# template.net
KiCad netlist of a schematic drawn in EAGLE
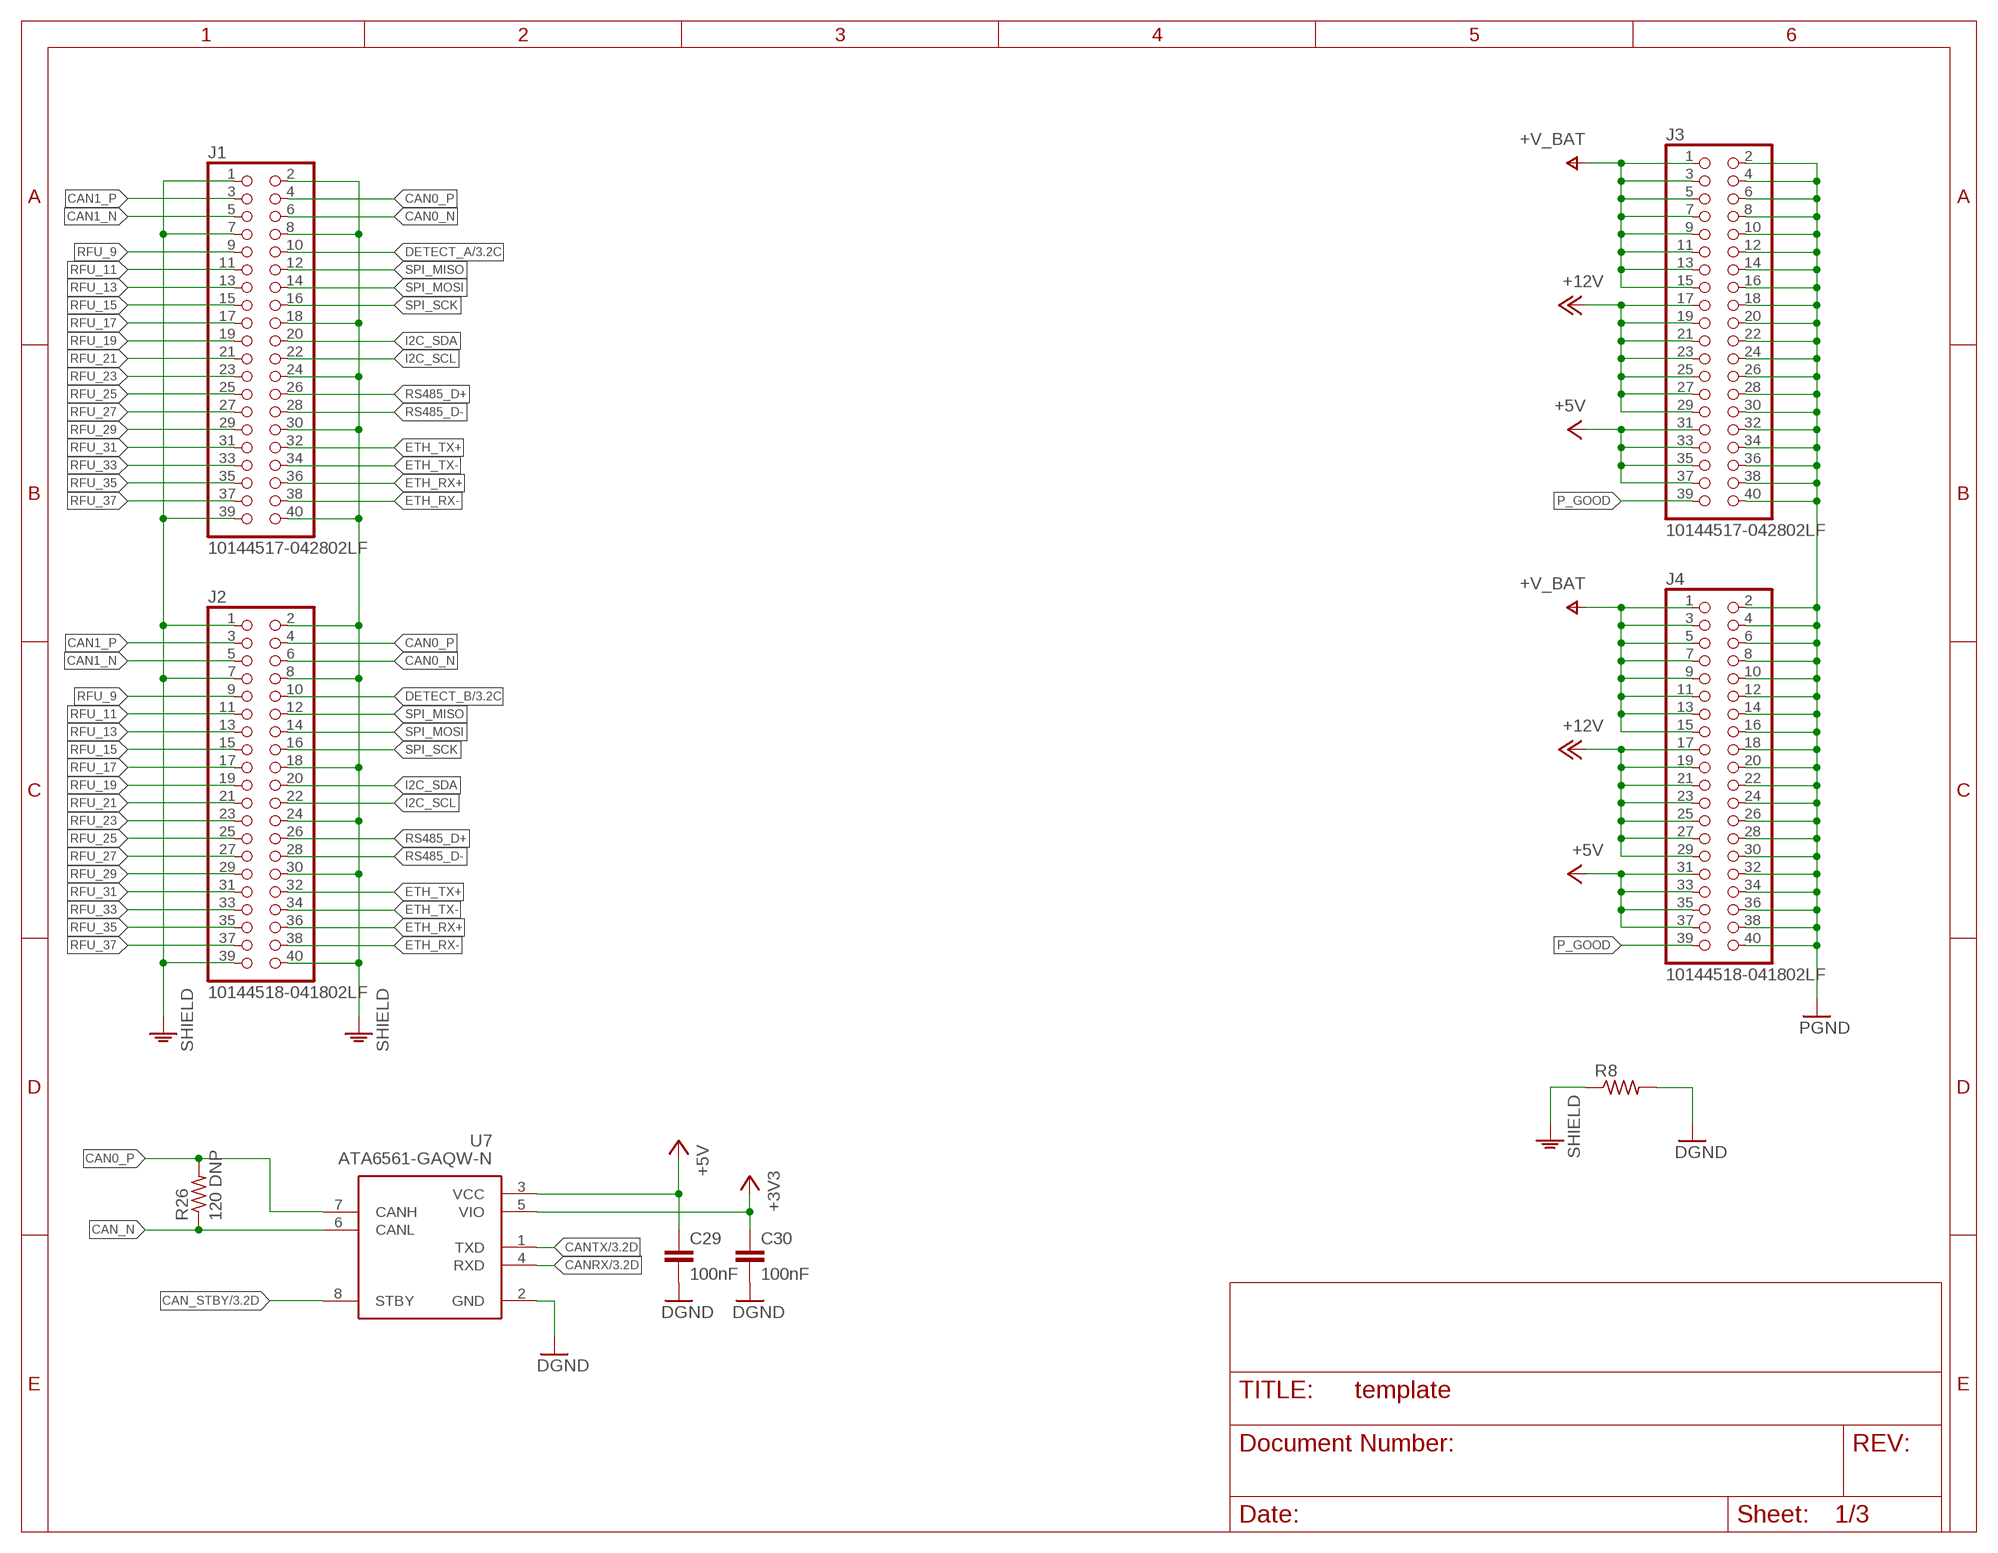
[diagram p0: schematic, sheet 1]
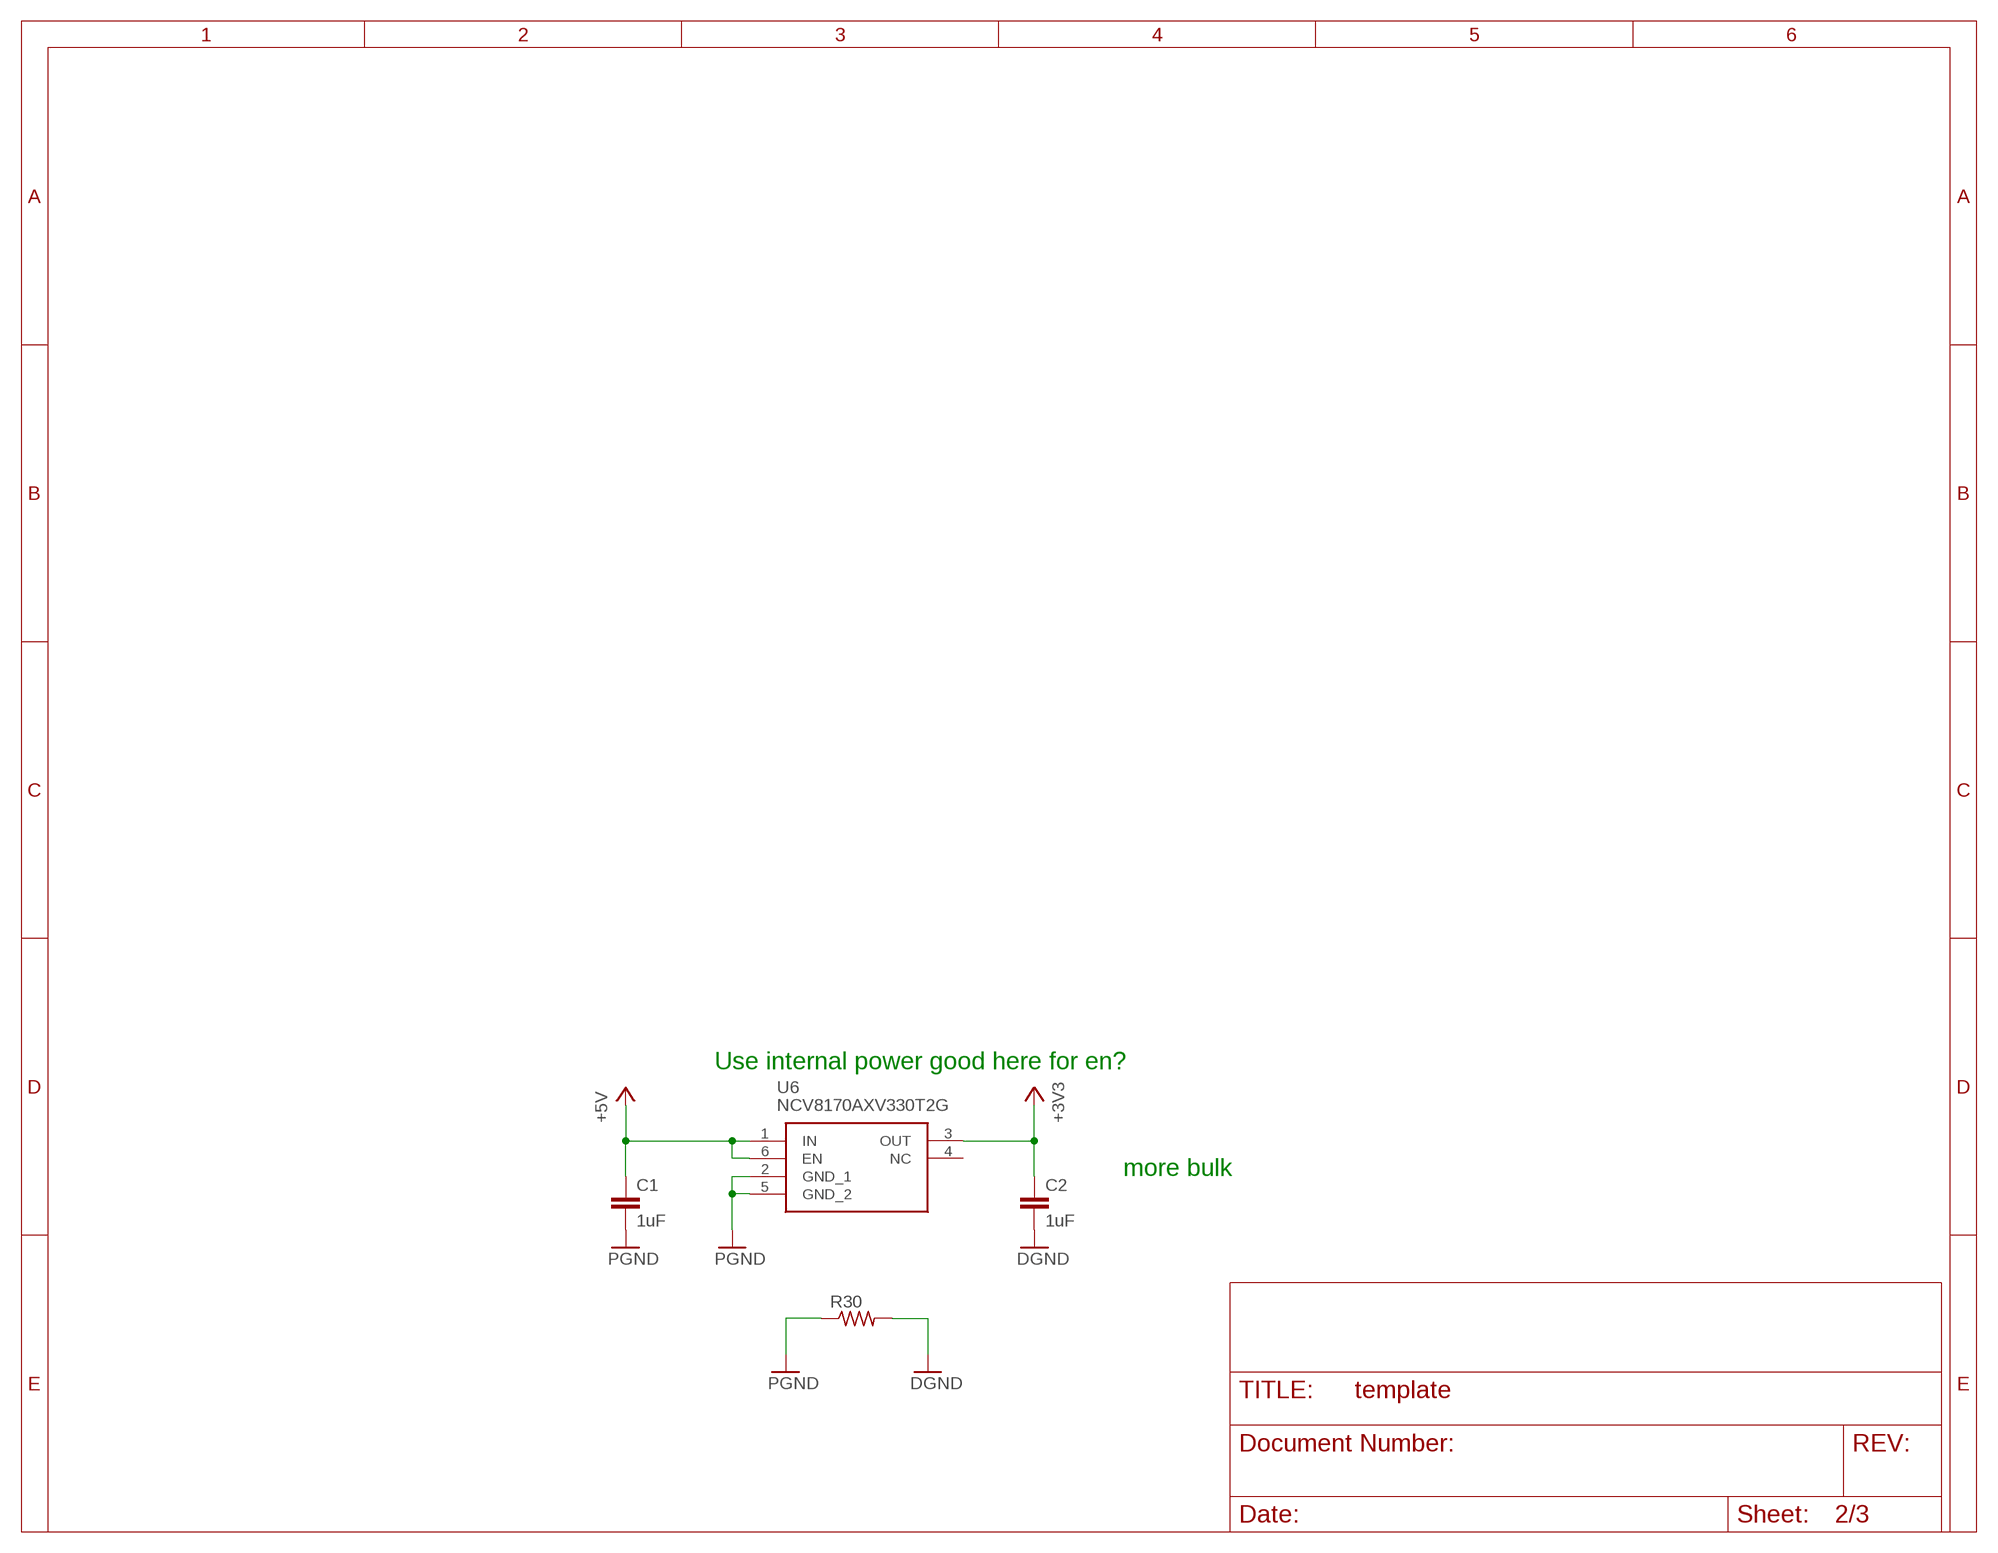
[diagram p1: schematic, sheet 2]
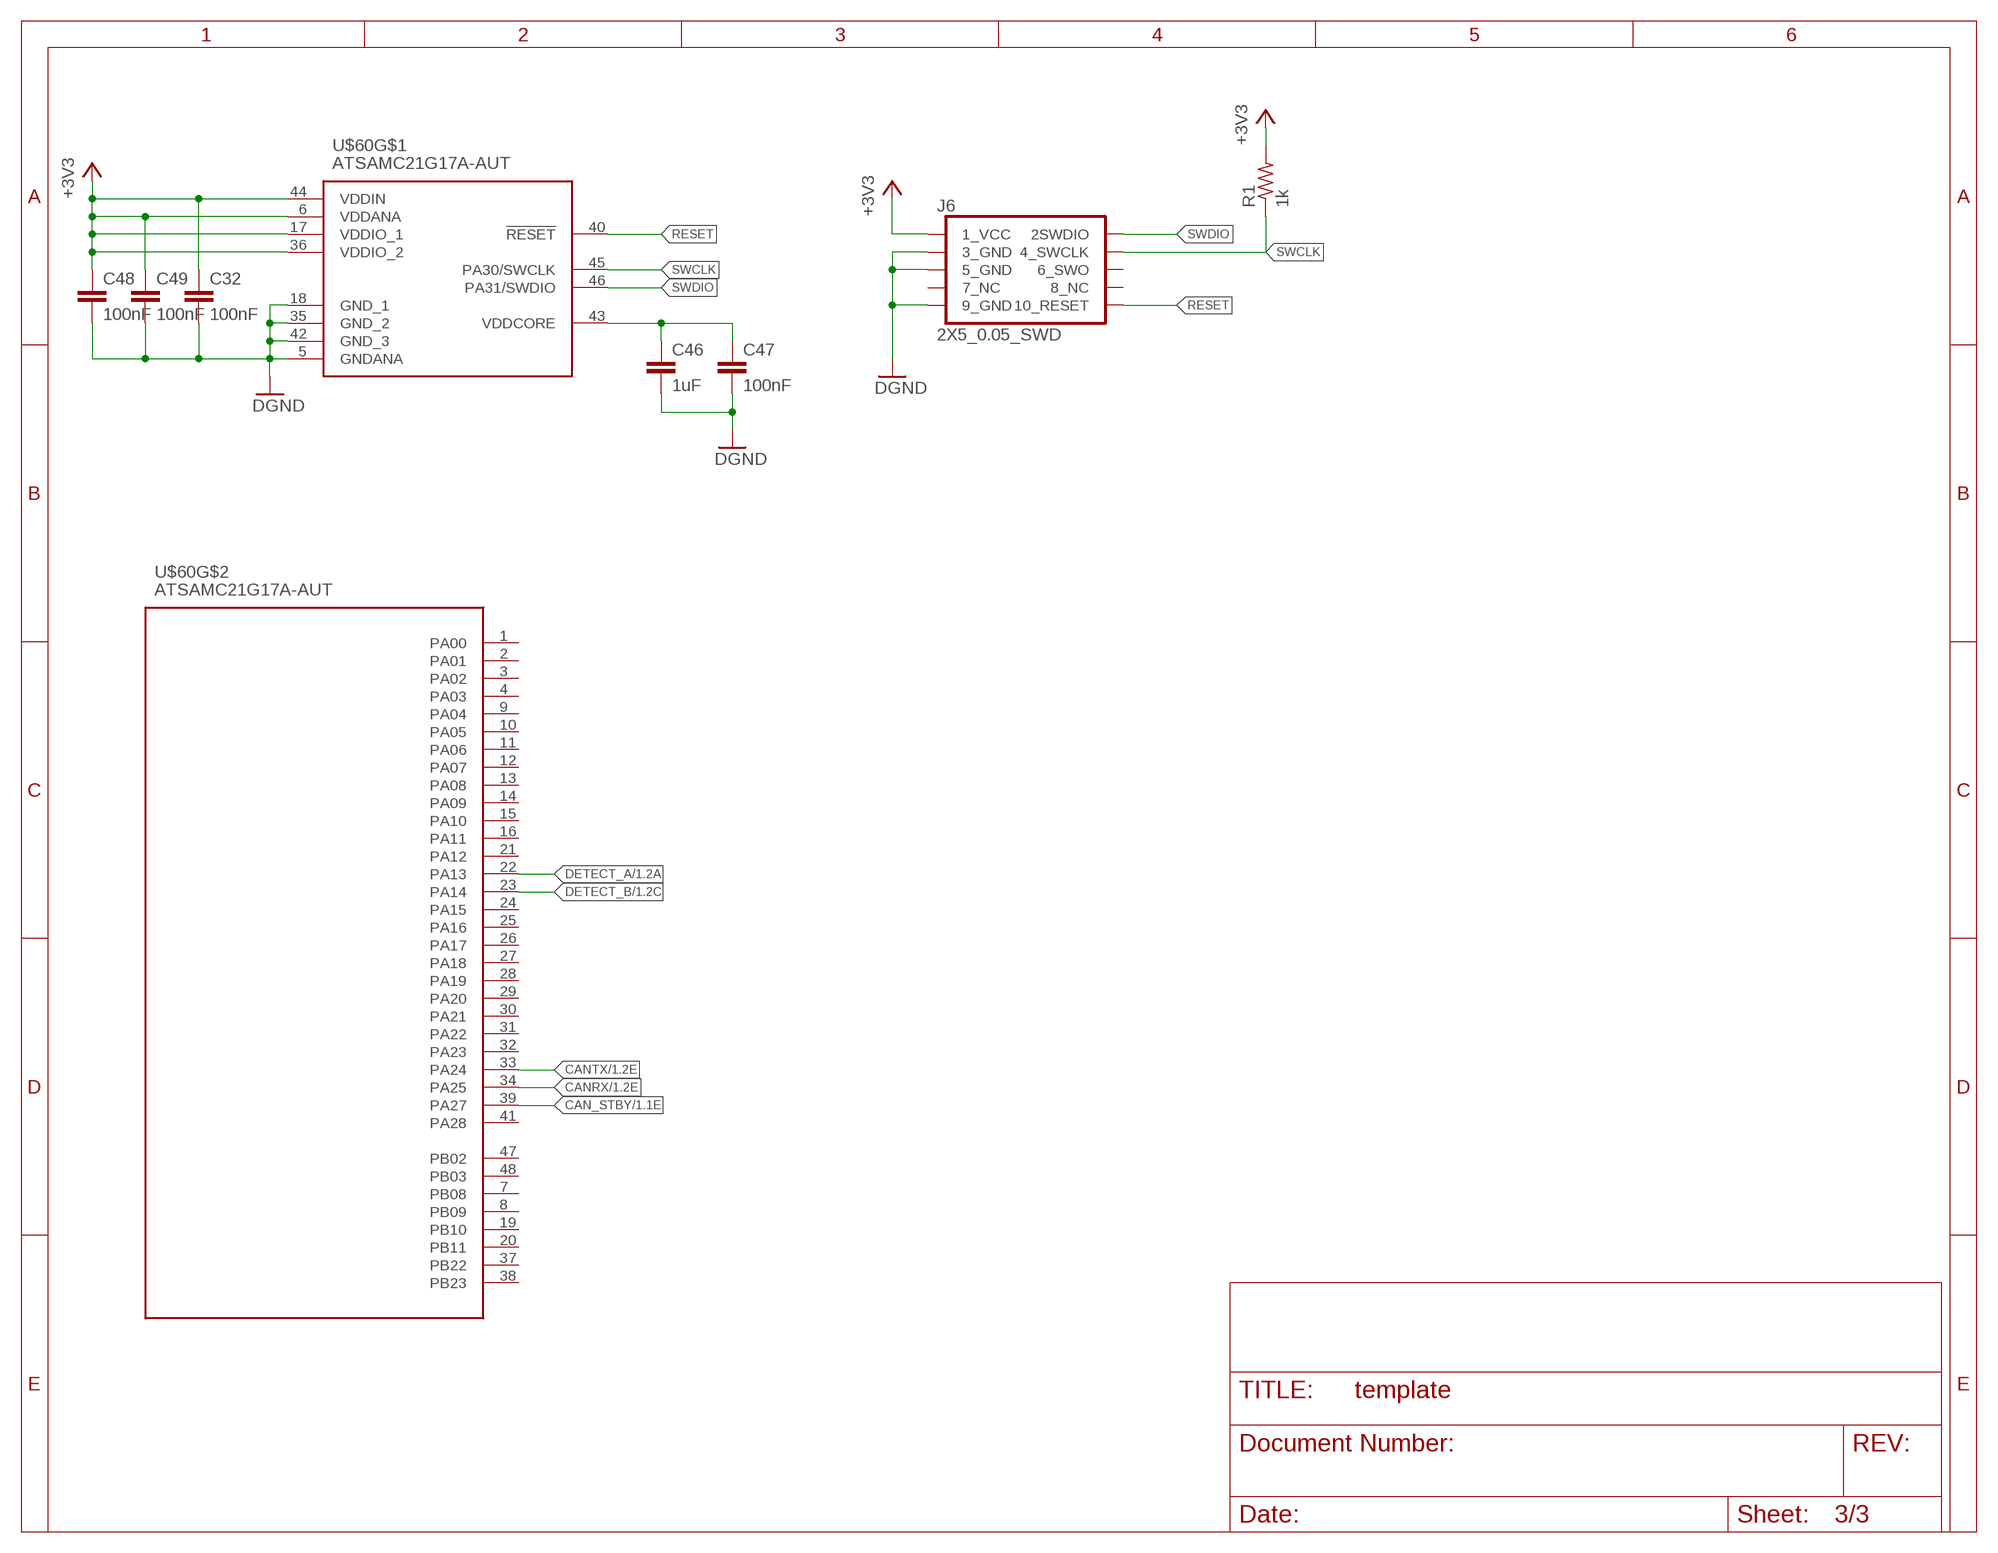
[diagram p2: schematic, sheet 3]

(export (version "E")
  (design (tool "Eeschema 10.0.6"))
  (components
    (comp (ref "C32")
      (value "100nF")
      (footprint "eagle-import:C0805")
      (libsource (lib "eagle-import") (part "C-EUC0805"))
    )
    (comp (ref "C46")
      (value "1uF")
      (footprint "eagle-import:C0805")
      (libsource (lib "eagle-import") (part "C-EUC0805"))
    )
    (comp (ref "C47")
      (value "100nF")
      (footprint "eagle-import:C0805")
      (libsource (lib "eagle-import") (part "C-EUC0805"))
    )
    (comp (ref "C48")
      (value "100nF")
      (footprint "eagle-import:C0805")
      (libsource (lib "eagle-import") (part "C-EUC0805"))
    )
    (comp (ref "C49")
      (value "100nF")
      (footprint "eagle-import:C0805")
      (libsource (lib "eagle-import") (part "C-EUC0805"))
    )
    (comp (ref "J6")
      (value "2X5_0.05_SWD")
      (footprint "eagle-import:2X5_RIGHT")
      (libsource (lib "eagle-import") (part "2X5_0.05_SWD"))
    )
    (comp (ref "R1")
      (value "1k")
      (footprint "eagle-import:R0402")
      (libsource (lib "eagle-import") (part "R-US_R0402"))
    )
    (comp (ref "U$60")
      (value "ATSAMC21G17A-AUT")
      (footprint "eagle-import:QFP50P900X900X120-48N")
      (libsource (lib "eagle-import") (part "ATSAMC21G17A-AUT"))
    )
    (comp (ref "C1")
      (value "1uF")
      (footprint "eagle-import:C0603")
      (libsource (lib "eagle-import") (part "C-EUC0603"))
    )
    (comp (ref "C2")
      (value "1uF")
      (footprint "eagle-import:C0603")
      (libsource (lib "eagle-import") (part "C-EUC0603"))
    )
    (comp (ref "R30")
      (value "R-US_R0402")
      (footprint "eagle-import:R0402")
      (libsource (lib "eagle-import") (part "R-US_R0402"))
    )
    (comp (ref "U6")
      (value "NCV8170AXV330T2G")
      (footprint "eagle-import:SOTFL50P160X60-6N")
      (fields (field (name "MOUSER_PART_NUMBER") "863-NCV8170AXV330T2G"))
      (libsource (lib "eagle-import") (part "NCV8170AXV330T2G"))
    )
    (comp (ref "C29")
      (value "100nF")
      (footprint "eagle-import:C0402")
      (libsource (lib "eagle-import") (part "C-EUC0402"))
    )
    (comp (ref "C30")
      (value "100nF")
      (footprint "eagle-import:C0402")
      (libsource (lib "eagle-import") (part "C-EUC0402"))
    )
    (comp (ref "J1")
      (value "10144517-042802LF")
      (footprint "eagle-import:10144517-042802LF")
      (libsource (lib "eagle-import") (part "10144517-042802LF"))
    )
    (comp (ref "J2")
      (value "10144518-041802LF")
      (footprint "eagle-import:10144518-041802LF")
      (libsource (lib "eagle-import") (part "10144518-041802LF"))
    )
    (comp (ref "J3")
      (value "10144517-042802LF")
      (footprint "eagle-import:10144517-042802LF")
      (libsource (lib "eagle-import") (part "10144517-042802LF"))
    )
    (comp (ref "J4")
      (value "10144518-041802LF")
      (footprint "eagle-import:10144518-041802LF")
      (libsource (lib "eagle-import") (part "10144518-041802LF"))
    )
    (comp (ref "R8")
      (value "R-US_R0402")
      (footprint "eagle-import:R0402")
      (libsource (lib "eagle-import") (part "R-US_R0402"))
    )
    (comp (ref "R26")
      (value "120 DNP")
      (footprint "eagle-import:R0402")
      (libsource (lib "eagle-import") (part "R-US_R0402"))
    )
    (comp (ref "U7")
      (value "ATA6561-GAQW-N")
      (footprint "eagle-import:SOIC127P600X175-8N")
      (fields (field (name "MOUSER_PART_NUMBER") "579-ATA6561-GAQW-N"))
      (libsource (lib "eagle-import") (part "ATA6561-GAQW-N"))
    )
  )
  (nets
    (net (code "1") (name "+3V3") (class "Default")
      (node (ref "C2") (pin "1") (pinfunction "1_1") (pintype "passive"))
      (node (ref "C30") (pin "1") (pinfunction "1_1") (pintype "passive"))
      (node (ref "C32") (pin "1") (pinfunction "1_1") (pintype "passive"))
      (node (ref "C48") (pin "1") (pinfunction "1_1") (pintype "passive"))
      (node (ref "C49") (pin "1") (pinfunction "1_1") (pintype "passive"))
      (node (ref "J6") (pin "1") (pinfunction "1_VCC_1") (pintype "passive"))
      (node (ref "R1") (pin "2") (pinfunction "2_2") (pintype "passive"))
      (node (ref "U$60") (pin "17") (pinfunction "VDDIO_1_17") (pintype "bidirectional"))
      (node (ref "U$60") (pin "36") (pinfunction "VDDIO_2_36") (pintype "bidirectional"))
      (node (ref "U$60") (pin "44") (pinfunction "VDDIN_44") (pintype "power_in"))
      (node (ref "U$60") (pin "6") (pinfunction "VDDANA_6") (pintype "power_in"))
      (node (ref "U6") (pin "3") (pinfunction "OUT_3") (pintype "bidirectional"))
      (node (ref "U7") (pin "5") (pinfunction "VIO_5") (pintype "bidirectional"))
    )
    (net (code "2") (name "+5V") (class "Default")
      (node (ref "C1") (pin "1") (pinfunction "1_1") (pintype "passive"))
      (node (ref "C29") (pin "1") (pinfunction "1_1") (pintype "passive"))
      (node (ref "J3") (pin "31") (pinfunction "31_31") (pintype "passive"))
      (node (ref "J3") (pin "33") (pinfunction "33_33") (pintype "passive"))
      (node (ref "J3") (pin "35") (pinfunction "35_35") (pintype "passive"))
      (node (ref "J3") (pin "37") (pinfunction "37_37") (pintype "passive"))
      (node (ref "J4") (pin "31") (pinfunction "31_31") (pintype "passive"))
      (node (ref "J4") (pin "33") (pinfunction "33_33") (pintype "passive"))
      (node (ref "J4") (pin "35") (pinfunction "35_35") (pintype "passive"))
      (node (ref "J4") (pin "37") (pinfunction "37_37") (pintype "passive"))
      (node (ref "U6") (pin "1") (pinfunction "IN_1") (pintype "bidirectional"))
      (node (ref "U6") (pin "6") (pinfunction "EN_6") (pintype "bidirectional"))
      (node (ref "U7") (pin "3") (pinfunction "VCC_3") (pintype "bidirectional"))
    )
    (net (code "3") (name "+12V") (class "Default")
      (node (ref "J3") (pin "17") (pinfunction "17_17") (pintype "passive"))
      (node (ref "J3") (pin "19") (pinfunction "19_19") (pintype "passive"))
      (node (ref "J3") (pin "21") (pinfunction "21_21") (pintype "passive"))
      (node (ref "J3") (pin "23") (pinfunction "23_23") (pintype "passive"))
      (node (ref "J3") (pin "25") (pinfunction "25_25") (pintype "passive"))
      (node (ref "J3") (pin "27") (pinfunction "27_27") (pintype "passive"))
      (node (ref "J3") (pin "29") (pinfunction "29_29") (pintype "passive"))
      (node (ref "J4") (pin "17") (pinfunction "17_17") (pintype "passive"))
      (node (ref "J4") (pin "19") (pinfunction "19_19") (pintype "passive"))
      (node (ref "J4") (pin "21") (pinfunction "21_21") (pintype "passive"))
      (node (ref "J4") (pin "23") (pinfunction "23_23") (pintype "passive"))
      (node (ref "J4") (pin "25") (pinfunction "25_25") (pintype "passive"))
      (node (ref "J4") (pin "27") (pinfunction "27_27") (pintype "passive"))
      (node (ref "J4") (pin "29") (pinfunction "29_29") (pintype "passive"))
    )
    (net (code "4") (name "+V_BAT") (class "Default")
      (node (ref "J3") (pin "1") (pinfunction "1_1") (pintype "passive"))
      (node (ref "J3") (pin "11") (pinfunction "11_11") (pintype "passive"))
      (node (ref "J3") (pin "13") (pinfunction "13_13") (pintype "passive"))
      (node (ref "J3") (pin "15") (pinfunction "15_15") (pintype "passive"))
      (node (ref "J3") (pin "3") (pinfunction "3_3") (pintype "passive"))
      (node (ref "J3") (pin "5") (pinfunction "5_5") (pintype "passive"))
      (node (ref "J3") (pin "7") (pinfunction "7_7") (pintype "passive"))
      (node (ref "J3") (pin "9") (pinfunction "9_9") (pintype "passive"))
      (node (ref "J4") (pin "1") (pinfunction "1_1") (pintype "passive"))
      (node (ref "J4") (pin "11") (pinfunction "11_11") (pintype "passive"))
      (node (ref "J4") (pin "13") (pinfunction "13_13") (pintype "passive"))
      (node (ref "J4") (pin "15") (pinfunction "15_15") (pintype "passive"))
      (node (ref "J4") (pin "3") (pinfunction "3_3") (pintype "passive"))
      (node (ref "J4") (pin "5") (pinfunction "5_5") (pintype "passive"))
      (node (ref "J4") (pin "7") (pinfunction "7_7") (pintype "passive"))
      (node (ref "J4") (pin "9") (pinfunction "9_9") (pintype "passive"))
    )
    (net (code "5") (name "CAN0_N") (class "Default")
      (node (ref "J1") (pin "6") (pinfunction "6_6") (pintype "passive"))
      (node (ref "J2") (pin "6") (pinfunction "6_6") (pintype "passive"))
    )
    (net (code "6") (name "CAN0_P") (class "Default")
      (node (ref "J1") (pin "4") (pinfunction "4_4") (pintype "passive"))
      (node (ref "J2") (pin "4") (pinfunction "4_4") (pintype "passive"))
      (node (ref "R26") (pin "2") (pinfunction "2_2") (pintype "passive"))
      (node (ref "U7") (pin "7") (pinfunction "CANH_7") (pintype "bidirectional"))
    )
    (net (code "7") (name "CAN1_N") (class "Default")
      (node (ref "J1") (pin "5") (pinfunction "5_5") (pintype "passive"))
      (node (ref "J2") (pin "5") (pinfunction "5_5") (pintype "passive"))
    )
    (net (code "8") (name "CAN1_P") (class "Default")
      (node (ref "J1") (pin "3") (pinfunction "3_3") (pintype "passive"))
      (node (ref "J2") (pin "3") (pinfunction "3_3") (pintype "passive"))
    )
    (net (code "9") (name "CANRX") (class "Default")
      (node (ref "U$60") (pin "34") (pinfunction "PA25_34") (pintype "bidirectional"))
      (node (ref "U7") (pin "4") (pinfunction "RXD_4") (pintype "bidirectional"))
    )
    (net (code "10") (name "CANTX") (class "Default")
      (node (ref "U$60") (pin "33") (pinfunction "PA24_33") (pintype "bidirectional"))
      (node (ref "U7") (pin "1") (pinfunction "TXD_1") (pintype "bidirectional"))
    )
    (net (code "11") (name "CAN_N") (class "Default")
      (node (ref "R26") (pin "1") (pinfunction "1_1") (pintype "passive"))
      (node (ref "U7") (pin "6") (pinfunction "CANL_6") (pintype "bidirectional"))
    )
    (net (code "12") (name "CAN_STBY") (class "Default")
      (node (ref "U$60") (pin "39") (pinfunction "PA27_39") (pintype "bidirectional"))
      (node (ref "U7") (pin "8") (pinfunction "STBY_8") (pintype "bidirectional"))
    )
    (net (code "13") (name "DETECT_A") (class "Default")
      (node (ref "J1") (pin "10") (pinfunction "10_10") (pintype "passive"))
      (node (ref "U$60") (pin "22") (pinfunction "PA13_22") (pintype "bidirectional"))
    )
    (net (code "14") (name "DETECT_B") (class "Default")
      (node (ref "J2") (pin "10") (pinfunction "10_10") (pintype "passive"))
      (node (ref "U$60") (pin "23") (pinfunction "PA14_23") (pintype "bidirectional"))
    )
    (net (code "15") (name "DGND") (class "Default")
      (node (ref "C2") (pin "2") (pinfunction "2_2") (pintype "passive"))
      (node (ref "C29") (pin "2") (pinfunction "2_2") (pintype "passive"))
      (node (ref "C30") (pin "2") (pinfunction "2_2") (pintype "passive"))
      (node (ref "C32") (pin "2") (pinfunction "2_2") (pintype "passive"))
      (node (ref "C46") (pin "2") (pinfunction "2_2") (pintype "passive"))
      (node (ref "C47") (pin "2") (pinfunction "2_2") (pintype "passive"))
      (node (ref "C48") (pin "2") (pinfunction "2_2") (pintype "passive"))
      (node (ref "C49") (pin "2") (pinfunction "2_2") (pintype "passive"))
      (node (ref "J6") (pin "3") (pinfunction "3_GND_3") (pintype "passive"))
      (node (ref "J6") (pin "5") (pinfunction "5_GND_5") (pintype "passive"))
      (node (ref "J6") (pin "9") (pinfunction "9_GND_9") (pintype "passive"))
      (node (ref "R30") (pin "2") (pinfunction "2_2") (pintype "passive"))
      (node (ref "R8") (pin "2") (pinfunction "2_2") (pintype "passive"))
      (node (ref "U$60") (pin "18") (pinfunction "GND_1_18") (pintype "power_in"))
      (node (ref "U$60") (pin "35") (pinfunction "GND_2_35") (pintype "power_in"))
      (node (ref "U$60") (pin "42") (pinfunction "GND_3_42") (pintype "bidirectional"))
      (node (ref "U$60") (pin "5") (pinfunction "GNDANA_5") (pintype "bidirectional"))
      (node (ref "U7") (pin "2") (pinfunction "GND_2") (pintype "bidirectional"))
    )
    (net (code "16") (name "ETH_RX+") (class "Default")
      (node (ref "J1") (pin "36") (pinfunction "36_36") (pintype "passive"))
      (node (ref "J2") (pin "36") (pinfunction "36_36") (pintype "passive"))
    )
    (net (code "17") (name "ETH_RX-") (class "Default")
      (node (ref "J1") (pin "38") (pinfunction "38_38") (pintype "passive"))
      (node (ref "J2") (pin "38") (pinfunction "38_38") (pintype "passive"))
    )
    (net (code "18") (name "ETH_TX+") (class "Default")
      (node (ref "J1") (pin "32") (pinfunction "32_32") (pintype "passive"))
      (node (ref "J2") (pin "32") (pinfunction "32_32") (pintype "passive"))
    )
    (net (code "19") (name "ETH_TX-") (class "Default")
      (node (ref "J1") (pin "34") (pinfunction "34_34") (pintype "passive"))
      (node (ref "J2") (pin "34") (pinfunction "34_34") (pintype "passive"))
    )
    (net (code "20") (name "I2C_SCL") (class "Default")
      (node (ref "J1") (pin "22") (pinfunction "22_22") (pintype "passive"))
      (node (ref "J2") (pin "22") (pinfunction "22_22") (pintype "passive"))
    )
    (net (code "21") (name "I2C_SDA") (class "Default")
      (node (ref "J1") (pin "20") (pinfunction "20_20") (pintype "passive"))
      (node (ref "J2") (pin "20") (pinfunction "20_20") (pintype "passive"))
    )
    (net (code "22") (name "Net-(U$60A-VDDCORE)") (class "Default")
      (node (ref "C46") (pin "1") (pinfunction "1_1") (pintype "passive"))
      (node (ref "C47") (pin "1") (pinfunction "1_1") (pintype "passive"))
      (node (ref "U$60") (pin "43") (pinfunction "VDDCORE_43") (pintype "power_in"))
    )
    (net (code "23") (name "PGND") (class "Default")
      (node (ref "C1") (pin "2") (pinfunction "2_2") (pintype "passive"))
      (node (ref "J3") (pin "10") (pinfunction "10_10") (pintype "passive"))
      (node (ref "J3") (pin "12") (pinfunction "12_12") (pintype "passive"))
      (node (ref "J3") (pin "14") (pinfunction "14_14") (pintype "passive"))
      (node (ref "J3") (pin "16") (pinfunction "16_16") (pintype "passive"))
      (node (ref "J3") (pin "18") (pinfunction "18_18") (pintype "passive"))
      (node (ref "J3") (pin "2") (pinfunction "2_2") (pintype "passive"))
      (node (ref "J3") (pin "20") (pinfunction "20_20") (pintype "passive"))
      (node (ref "J3") (pin "22") (pinfunction "22_22") (pintype "passive"))
      (node (ref "J3") (pin "24") (pinfunction "24_24") (pintype "passive"))
      (node (ref "J3") (pin "26") (pinfunction "26_26") (pintype "passive"))
      (node (ref "J3") (pin "28") (pinfunction "28_28") (pintype "passive"))
      (node (ref "J3") (pin "30") (pinfunction "30_30") (pintype "passive"))
      (node (ref "J3") (pin "32") (pinfunction "32_32") (pintype "passive"))
      (node (ref "J3") (pin "34") (pinfunction "34_34") (pintype "passive"))
      (node (ref "J3") (pin "36") (pinfunction "36_36") (pintype "passive"))
      (node (ref "J3") (pin "38") (pinfunction "38_38") (pintype "passive"))
      (node (ref "J3") (pin "4") (pinfunction "4_4") (pintype "passive"))
      (node (ref "J3") (pin "40") (pinfunction "40_40") (pintype "passive"))
      (node (ref "J3") (pin "6") (pinfunction "6_6") (pintype "passive"))
      (node (ref "J3") (pin "8") (pinfunction "8_8") (pintype "passive"))
      (node (ref "J4") (pin "10") (pinfunction "10_10") (pintype "passive"))
      (node (ref "J4") (pin "12") (pinfunction "12_12") (pintype "passive"))
      (node (ref "J4") (pin "14") (pinfunction "14_14") (pintype "passive"))
      (node (ref "J4") (pin "16") (pinfunction "16_16") (pintype "passive"))
      (node (ref "J4") (pin "18") (pinfunction "18_18") (pintype "passive"))
      (node (ref "J4") (pin "2") (pinfunction "2_2") (pintype "passive"))
      (node (ref "J4") (pin "20") (pinfunction "20_20") (pintype "passive"))
      (node (ref "J4") (pin "22") (pinfunction "22_22") (pintype "passive"))
      (node (ref "J4") (pin "24") (pinfunction "24_24") (pintype "passive"))
      (node (ref "J4") (pin "26") (pinfunction "26_26") (pintype "passive"))
      (node (ref "J4") (pin "28") (pinfunction "28_28") (pintype "passive"))
      (node (ref "J4") (pin "30") (pinfunction "30_30") (pintype "passive"))
      (node (ref "J4") (pin "32") (pinfunction "32_32") (pintype "passive"))
      (node (ref "J4") (pin "34") (pinfunction "34_34") (pintype "passive"))
      (node (ref "J4") (pin "36") (pinfunction "36_36") (pintype "passive"))
      (node (ref "J4") (pin "38") (pinfunction "38_38") (pintype "passive"))
      (node (ref "J4") (pin "4") (pinfunction "4_4") (pintype "passive"))
      (node (ref "J4") (pin "40") (pinfunction "40_40") (pintype "passive"))
      (node (ref "J4") (pin "6") (pinfunction "6_6") (pintype "passive"))
      (node (ref "J4") (pin "8") (pinfunction "8_8") (pintype "passive"))
      (node (ref "R30") (pin "1") (pinfunction "1_1") (pintype "passive"))
      (node (ref "U6") (pin "2") (pinfunction "GND_1_2") (pintype "bidirectional"))
      (node (ref "U6") (pin "5") (pinfunction "GND_2_5") (pintype "bidirectional"))
    )
    (net (code "24") (name "P_GOOD") (class "Default")
      (node (ref "J3") (pin "39") (pinfunction "39_39") (pintype "passive"))
      (node (ref "J4") (pin "39") (pinfunction "39_39") (pintype "passive"))
    )
    (net (code "25") (name "RESET") (class "Default")
      (node (ref "J6") (pin "10") (pinfunction "10_RESET_10") (pintype "passive"))
      (node (ref "U$60") (pin "40") (pinfunction "~{RESET}_40") (pintype "input"))
    )
    (net (code "26") (name "RFU_9") (class "Default")
      (node (ref "J1") (pin "9") (pinfunction "9_9") (pintype "passive"))
      (node (ref "J2") (pin "9") (pinfunction "9_9") (pintype "passive"))
    )
    (net (code "27") (name "RFU_11") (class "Default")
      (node (ref "J1") (pin "11") (pinfunction "11_11") (pintype "passive"))
      (node (ref "J2") (pin "11") (pinfunction "11_11") (pintype "passive"))
    )
    (net (code "28") (name "RFU_13") (class "Default")
      (node (ref "J1") (pin "13") (pinfunction "13_13") (pintype "passive"))
      (node (ref "J2") (pin "13") (pinfunction "13_13") (pintype "passive"))
    )
    (net (code "29") (name "RFU_15") (class "Default")
      (node (ref "J1") (pin "15") (pinfunction "15_15") (pintype "passive"))
      (node (ref "J2") (pin "15") (pinfunction "15_15") (pintype "passive"))
    )
    (net (code "30") (name "RFU_17") (class "Default")
      (node (ref "J1") (pin "17") (pinfunction "17_17") (pintype "passive"))
      (node (ref "J2") (pin "17") (pinfunction "17_17") (pintype "passive"))
    )
    (net (code "31") (name "RFU_19") (class "Default")
      (node (ref "J1") (pin "19") (pinfunction "19_19") (pintype "passive"))
      (node (ref "J2") (pin "19") (pinfunction "19_19") (pintype "passive"))
    )
    (net (code "32") (name "RFU_21") (class "Default")
      (node (ref "J1") (pin "21") (pinfunction "21_21") (pintype "passive"))
      (node (ref "J2") (pin "21") (pinfunction "21_21") (pintype "passive"))
    )
    (net (code "33") (name "RFU_23") (class "Default")
      (node (ref "J1") (pin "23") (pinfunction "23_23") (pintype "passive"))
      (node (ref "J2") (pin "23") (pinfunction "23_23") (pintype "passive"))
    )
    (net (code "34") (name "RFU_25") (class "Default")
      (node (ref "J1") (pin "25") (pinfunction "25_25") (pintype "passive"))
      (node (ref "J2") (pin "25") (pinfunction "25_25") (pintype "passive"))
    )
    (net (code "35") (name "RFU_27") (class "Default")
      (node (ref "J1") (pin "27") (pinfunction "27_27") (pintype "passive"))
      (node (ref "J2") (pin "27") (pinfunction "27_27") (pintype "passive"))
    )
    (net (code "36") (name "RFU_29") (class "Default")
      (node (ref "J1") (pin "29") (pinfunction "29_29") (pintype "passive"))
      (node (ref "J2") (pin "29") (pinfunction "29_29") (pintype "passive"))
    )
    (net (code "37") (name "RFU_31") (class "Default")
      (node (ref "J1") (pin "31") (pinfunction "31_31") (pintype "passive"))
      (node (ref "J2") (pin "31") (pinfunction "31_31") (pintype "passive"))
    )
    (net (code "38") (name "RFU_33") (class "Default")
      (node (ref "J1") (pin "33") (pinfunction "33_33") (pintype "passive"))
      (node (ref "J2") (pin "33") (pinfunction "33_33") (pintype "passive"))
    )
    (net (code "39") (name "RFU_35") (class "Default")
      (node (ref "J1") (pin "35") (pinfunction "35_35") (pintype "passive"))
      (node (ref "J2") (pin "35") (pinfunction "35_35") (pintype "passive"))
    )
    (net (code "40") (name "RFU_37") (class "Default")
      (node (ref "J1") (pin "37") (pinfunction "37_37") (pintype "passive"))
      (node (ref "J2") (pin "37") (pinfunction "37_37") (pintype "passive"))
    )
    (net (code "41") (name "RS485_D+") (class "Default")
      (node (ref "J1") (pin "26") (pinfunction "26_26") (pintype "passive"))
      (node (ref "J2") (pin "26") (pinfunction "26_26") (pintype "passive"))
    )
    (net (code "42") (name "RS485_D-") (class "Default")
      (node (ref "J1") (pin "28") (pinfunction "28_28") (pintype "passive"))
      (node (ref "J2") (pin "28") (pinfunction "28_28") (pintype "passive"))
    )
    (net (code "43") (name "SHIELD") (class "Default")
      (node (ref "J1") (pin "1") (pinfunction "1_1") (pintype "passive"))
      (node (ref "J1") (pin "18") (pinfunction "18_18") (pintype "passive"))
      (node (ref "J1") (pin "2") (pinfunction "2_2") (pintype "passive"))
      (node (ref "J1") (pin "24") (pinfunction "24_24") (pintype "passive"))
      (node (ref "J1") (pin "30") (pinfunction "30_30") (pintype "passive"))
      (node (ref "J1") (pin "39") (pinfunction "39_39") (pintype "passive"))
      (node (ref "J1") (pin "40") (pinfunction "40_40") (pintype "passive"))
      (node (ref "J1") (pin "7") (pinfunction "7_7") (pintype "passive"))
      (node (ref "J1") (pin "8") (pinfunction "8_8") (pintype "passive"))
      (node (ref "J2") (pin "1") (pinfunction "1_1") (pintype "passive"))
      (node (ref "J2") (pin "18") (pinfunction "18_18") (pintype "passive"))
      (node (ref "J2") (pin "2") (pinfunction "2_2") (pintype "passive"))
      (node (ref "J2") (pin "24") (pinfunction "24_24") (pintype "passive"))
      (node (ref "J2") (pin "30") (pinfunction "30_30") (pintype "passive"))
      (node (ref "J2") (pin "39") (pinfunction "39_39") (pintype "passive"))
      (node (ref "J2") (pin "40") (pinfunction "40_40") (pintype "passive"))
      (node (ref "J2") (pin "7") (pinfunction "7_7") (pintype "passive"))
      (node (ref "J2") (pin "8") (pinfunction "8_8") (pintype "passive"))
      (node (ref "R8") (pin "1") (pinfunction "1_1") (pintype "passive"))
    )
    (net (code "44") (name "SPI_MISO") (class "Default")
      (node (ref "J1") (pin "12") (pinfunction "12_12") (pintype "passive"))
      (node (ref "J2") (pin "12") (pinfunction "12_12") (pintype "passive"))
    )
    (net (code "45") (name "SPI_MOSI") (class "Default")
      (node (ref "J1") (pin "14") (pinfunction "14_14") (pintype "passive"))
      (node (ref "J2") (pin "14") (pinfunction "14_14") (pintype "passive"))
    )
    (net (code "46") (name "SPI_SCK") (class "Default")
      (node (ref "J1") (pin "16") (pinfunction "16_16") (pintype "passive"))
      (node (ref "J2") (pin "16") (pinfunction "16_16") (pintype "passive"))
    )
    (net (code "47") (name "SWCLK") (class "Default")
      (node (ref "J6") (pin "4") (pinfunction "4_SWCLK_4") (pintype "passive"))
      (node (ref "R1") (pin "1") (pinfunction "1_1") (pintype "passive"))
      (node (ref "U$60") (pin "45") (pinfunction "PA30/SWCLK_45") (pintype "bidirectional"))
    )
    (net (code "48") (name "SWDIO") (class "Default")
      (node (ref "J6") (pin "2") (pinfunction "2SWDIO_2") (pintype "passive"))
      (node (ref "U$60") (pin "46") (pinfunction "PA31/SWDIO_46") (pintype "bidirectional"))
    )
    (net (code "49") (name "unconnected-(J6-6_SWO-Pad6)") (class "Default")
      (node (ref "J6") (pin "6") (pinfunction "6_SWO_6") (pintype "passive"))
    )
    (net (code "50") (name "unconnected-(J6-7_NC-Pad7)") (class "Default")
      (node (ref "J6") (pin "7") (pinfunction "7_NC_7") (pintype "passive"))
    )
    (net (code "51") (name "unconnected-(J6-8_NC-Pad8)") (class "Default")
      (node (ref "J6") (pin "8") (pinfunction "8_NC_8") (pintype "passive"))
    )
    (net (code "52") (name "unconnected-(U$60B-PA00-Pad1)") (class "Default")
      (node (ref "U$60") (pin "1") (pinfunction "PA00_1") (pintype "bidirectional"))
    )
    (net (code "53") (name "unconnected-(U$60B-PA01-Pad2)") (class "Default")
      (node (ref "U$60") (pin "2") (pinfunction "PA01_2") (pintype "bidirectional"))
    )
    (net (code "54") (name "unconnected-(U$60B-PA02-Pad3)") (class "Default")
      (node (ref "U$60") (pin "3") (pinfunction "PA02_3") (pintype "bidirectional"))
    )
    (net (code "55") (name "unconnected-(U$60B-PA03-Pad4)") (class "Default")
      (node (ref "U$60") (pin "4") (pinfunction "PA03_4") (pintype "bidirectional"))
    )
    (net (code "56") (name "unconnected-(U$60B-PA04-Pad9)") (class "Default")
      (node (ref "U$60") (pin "9") (pinfunction "PA04_9") (pintype "bidirectional"))
    )
    (net (code "57") (name "unconnected-(U$60B-PA05-Pad10)") (class "Default")
      (node (ref "U$60") (pin "10") (pinfunction "PA05_10") (pintype "bidirectional"))
    )
    (net (code "58") (name "unconnected-(U$60B-PA06-Pad11)") (class "Default")
      (node (ref "U$60") (pin "11") (pinfunction "PA06_11") (pintype "bidirectional"))
    )
    (net (code "59") (name "unconnected-(U$60B-PA07-Pad12)") (class "Default")
      (node (ref "U$60") (pin "12") (pinfunction "PA07_12") (pintype "bidirectional"))
    )
    (net (code "60") (name "unconnected-(U$60B-PA08-Pad13)") (class "Default")
      (node (ref "U$60") (pin "13") (pinfunction "PA08_13") (pintype "bidirectional"))
    )
    (net (code "61") (name "unconnected-(U$60B-PA09-Pad14)") (class "Default")
      (node (ref "U$60") (pin "14") (pinfunction "PA09_14") (pintype "bidirectional"))
    )
    (net (code "62") (name "unconnected-(U$60B-PA10-Pad15)") (class "Default")
      (node (ref "U$60") (pin "15") (pinfunction "PA10_15") (pintype "bidirectional"))
    )
    (net (code "63") (name "unconnected-(U$60B-PA11-Pad16)") (class "Default")
      (node (ref "U$60") (pin "16") (pinfunction "PA11_16") (pintype "bidirectional"))
    )
    (net (code "64") (name "unconnected-(U$60B-PA12-Pad21)") (class "Default")
      (node (ref "U$60") (pin "21") (pinfunction "PA12_21") (pintype "bidirectional"))
    )
    (net (code "65") (name "unconnected-(U$60B-PA15-Pad24)") (class "Default")
      (node (ref "U$60") (pin "24") (pinfunction "PA15_24") (pintype "bidirectional"))
    )
    (net (code "66") (name "unconnected-(U$60B-PA16-Pad25)") (class "Default")
      (node (ref "U$60") (pin "25") (pinfunction "PA16_25") (pintype "bidirectional"))
    )
    (net (code "67") (name "unconnected-(U$60B-PA17-Pad26)") (class "Default")
      (node (ref "U$60") (pin "26") (pinfunction "PA17_26") (pintype "bidirectional"))
    )
    (net (code "68") (name "unconnected-(U$60B-PA18-Pad27)") (class "Default")
      (node (ref "U$60") (pin "27") (pinfunction "PA18_27") (pintype "bidirectional"))
    )
    (net (code "69") (name "unconnected-(U$60B-PA19-Pad28)") (class "Default")
      (node (ref "U$60") (pin "28") (pinfunction "PA19_28") (pintype "bidirectional"))
    )
    (net (code "70") (name "unconnected-(U$60B-PA20-Pad29)") (class "Default")
      (node (ref "U$60") (pin "29") (pinfunction "PA20_29") (pintype "bidirectional"))
    )
    (net (code "71") (name "unconnected-(U$60B-PA21-Pad30)") (class "Default")
      (node (ref "U$60") (pin "30") (pinfunction "PA21_30") (pintype "bidirectional"))
    )
    (net (code "72") (name "unconnected-(U$60B-PA22-Pad31)") (class "Default")
      (node (ref "U$60") (pin "31") (pinfunction "PA22_31") (pintype "bidirectional"))
    )
    (net (code "73") (name "unconnected-(U$60B-PA23-Pad32)") (class "Default")
      (node (ref "U$60") (pin "32") (pinfunction "PA23_32") (pintype "bidirectional"))
    )
    (net (code "74") (name "unconnected-(U$60B-PA28-Pad41)") (class "Default")
      (node (ref "U$60") (pin "41") (pinfunction "PA28_41") (pintype "bidirectional"))
    )
    (net (code "75") (name "unconnected-(U$60B-PB02-Pad47)") (class "Default")
      (node (ref "U$60") (pin "47") (pinfunction "PB02_47") (pintype "bidirectional"))
    )
    (net (code "76") (name "unconnected-(U$60B-PB03-Pad48)") (class "Default")
      (node (ref "U$60") (pin "48") (pinfunction "PB03_48") (pintype "bidirectional"))
    )
    (net (code "77") (name "unconnected-(U$60B-PB08-Pad7)") (class "Default")
      (node (ref "U$60") (pin "7") (pinfunction "PB08_7") (pintype "bidirectional"))
    )
    (net (code "78") (name "unconnected-(U$60B-PB09-Pad8)") (class "Default")
      (node (ref "U$60") (pin "8") (pinfunction "PB09_8") (pintype "bidirectional"))
    )
    (net (code "79") (name "unconnected-(U$60B-PB10-Pad19)") (class "Default")
      (node (ref "U$60") (pin "19") (pinfunction "PB10_19") (pintype "bidirectional"))
    )
    (net (code "80") (name "unconnected-(U$60B-PB11-Pad20)") (class "Default")
      (node (ref "U$60") (pin "20") (pinfunction "PB11_20") (pintype "bidirectional"))
    )
    (net (code "81") (name "unconnected-(U$60B-PB22-Pad37)") (class "Default")
      (node (ref "U$60") (pin "37") (pinfunction "PB22_37") (pintype "bidirectional"))
    )
    (net (code "82") (name "unconnected-(U$60B-PB23-Pad38)") (class "Default")
      (node (ref "U$60") (pin "38") (pinfunction "PB23_38") (pintype "bidirectional"))
    )
    (net (code "83") (name "unconnected-(U6-NC-Pad4)") (class "Default")
      (node (ref "U6") (pin "4") (pinfunction "NC_4") (pintype "no_connect"))
    )
  )
)
